# 15-SDRAM_Flash.net
KiCad netlist of a schematic drawn in Altium Designer
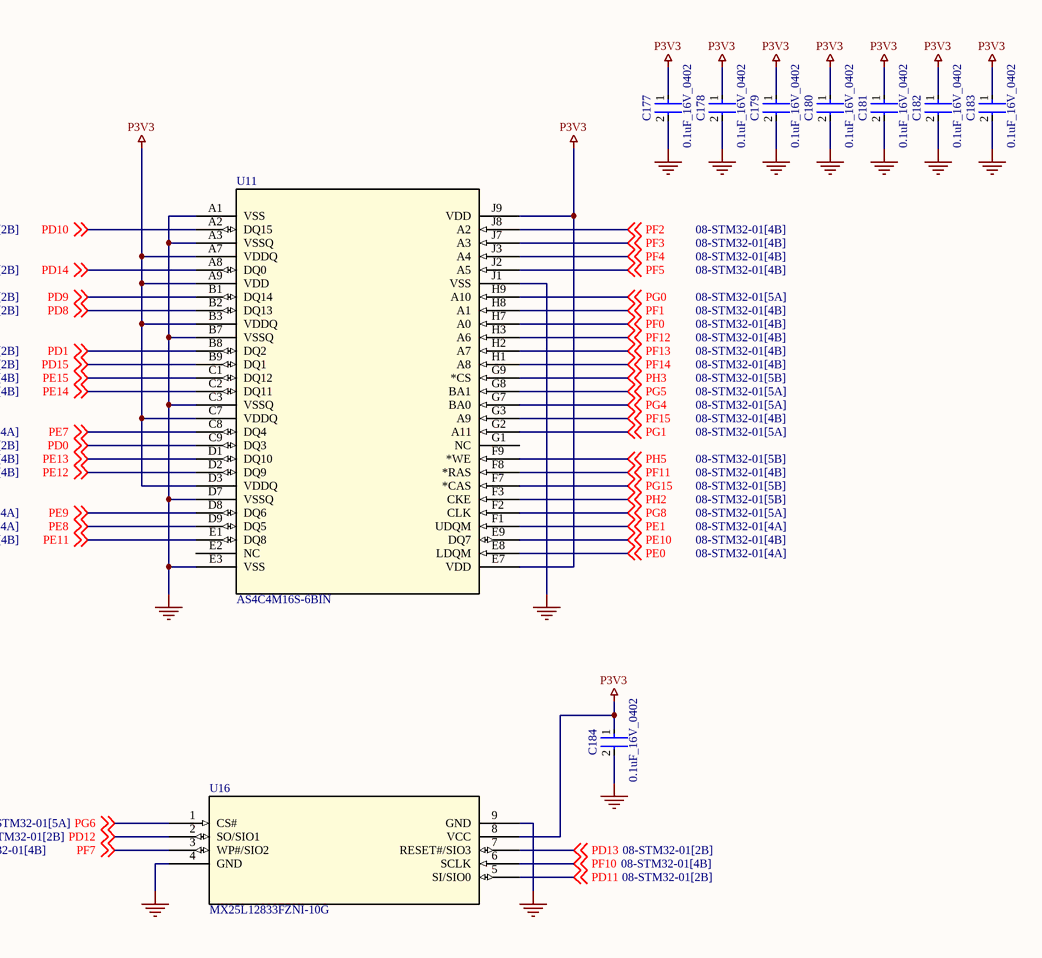
[diagram p0: 15-SDRAM_Flash.SchDoc]

(export (version "E")
  (design (tool "Eeschema 10.0.6"))
  (components
    (comp (ref "C177")
      (value "0.1uF_16V_0402")
      (footprint "FP-C0402-BB-MFG")
      (description "CAP CER 0.1UF 16V 5% X7R 0402")
      (fields
        (field (name "MANUFACTURER") "Kemet")
        (field (name "MANUFACTURER PART NUMBER") "C0402C104J4RACTU")
      )
      (libsource (lib "Altium Content Vault") (part "b4654b650e69147ec39a6b967a45e02"))
    )
    (comp (ref "C178")
      (value "0.1uF_16V_0402")
      (footprint "FP-C0402-BB-MFG")
      (description "CAP CER 0.1UF 16V 5% X7R 0402")
      (fields
        (field (name "MANUFACTURER") "Kemet")
        (field (name "MANUFACTURER PART NUMBER") "C0402C104J4RACTU")
      )
      (libsource (lib "Altium Content Vault") (part "b4654b650e69147ec39a6b967a45e02"))
    )
    (comp (ref "C179")
      (value "0.1uF_16V_0402")
      (footprint "FP-C0402-BB-MFG")
      (description "CAP CER 0.1UF 16V 5% X7R 0402")
      (fields
        (field (name "MANUFACTURER") "Kemet")
        (field (name "MANUFACTURER PART NUMBER") "C0402C104J4RACTU")
      )
      (libsource (lib "Altium Content Vault") (part "b4654b650e69147ec39a6b967a45e02"))
    )
    (comp (ref "C180")
      (value "0.1uF_16V_0402")
      (footprint "FP-C0402-BB-MFG")
      (description "CAP CER 0.1UF 16V 5% X7R 0402")
      (fields
        (field (name "MANUFACTURER") "Kemet")
        (field (name "MANUFACTURER PART NUMBER") "C0402C104J4RACTU")
      )
      (libsource (lib "Altium Content Vault") (part "b4654b650e69147ec39a6b967a45e02"))
    )
    (comp (ref "C181")
      (value "0.1uF_16V_0402")
      (footprint "FP-C0402-BB-MFG")
      (description "CAP CER 0.1UF 16V 5% X7R 0402")
      (fields
        (field (name "MANUFACTURER") "Kemet")
        (field (name "MANUFACTURER PART NUMBER") "C0402C104J4RACTU")
      )
      (libsource (lib "Altium Content Vault") (part "b4654b650e69147ec39a6b967a45e02"))
    )
    (comp (ref "C182")
      (value "0.1uF_16V_0402")
      (footprint "FP-C0402-BB-MFG")
      (description "CAP CER 0.1UF 16V 5% X7R 0402")
      (fields
        (field (name "MANUFACTURER") "Kemet")
        (field (name "MANUFACTURER PART NUMBER") "C0402C104J4RACTU")
      )
      (libsource (lib "Altium Content Vault") (part "b4654b650e69147ec39a6b967a45e02"))
    )
    (comp (ref "C183")
      (value "0.1uF_16V_0402")
      (footprint "FP-C0402-BB-MFG")
      (description "CAP CER 0.1UF 16V 5% X7R 0402")
      (fields
        (field (name "MANUFACTURER") "Kemet")
        (field (name "MANUFACTURER PART NUMBER") "C0402C104J4RACTU")
      )
      (libsource (lib "Altium Content Vault") (part "b4654b650e69147ec39a6b967a45e02"))
    )
    (comp (ref "C184")
      (value "0.1uF_16V_0402")
      (footprint "FP-C0402-BB-MFG")
      (description "CAP CER 0.1UF 16V 5% X7R 0402")
      (fields
        (field (name "MANUFACTURER") "Kemet")
        (field (name "MANUFACTURER PART NUMBER") "C0402C104J4RACTU")
      )
      (libsource (lib "Altium Content Vault") (part "b4654b650e69147ec39a6b967a45e02"))
    )
    (comp (ref "U11")
      (value "AS4C4M16S-6BIN")
      (footprint "TFBGA-54_8X8_ALL")
      (description "No Description Available")
      (fields (field (name "COPYRIGHT") "Copyright (C) 2023 Ultra Librarian. All rights reserved."))
      (libsource (lib "AS4C4M16S-6BIN") (part "AS4C4M16S-6BIN"))
    )
    (comp (ref "U16")
      (value "MX25L12833FZNI-10G")
      (footprint "WSON8_6X5X0p8_MAC")
      (description "No Description Available")
      (fields (field (name "COPYRIGHT") "Copyright (C) 2023 Ultra Librarian. All rights reserved."))
      (libsource (lib "MX25L12833FZNI-10G") (part "MX25L12833FZNI-10G"))
    )
  )
  (nets
    (net (code "1") (name "GND") (class "Default")
      (node (ref "C177") (pin "2") (pinfunction "2_2") (pintype "passive"))
      (node (ref "C178") (pin "2") (pinfunction "2_2") (pintype "passive"))
      (node (ref "C179") (pin "2") (pinfunction "2_2") (pintype "passive"))
      (node (ref "C180") (pin "2") (pinfunction "2_2") (pintype "passive"))
      (node (ref "C181") (pin "2") (pinfunction "2_2") (pintype "passive"))
      (node (ref "C182") (pin "2") (pinfunction "2_2") (pintype "passive"))
      (node (ref "C183") (pin "2") (pinfunction "2_2") (pintype "passive"))
      (node (ref "C184") (pin "2") (pinfunction "2_2") (pintype "passive"))
      (node (ref "U11") (pin "A1") (pinfunction "VSS_A1") (pintype "power_in"))
      (node (ref "U11") (pin "A3") (pinfunction "VSSQ_A3") (pintype "power_in"))
      (node (ref "U11") (pin "B7") (pinfunction "VSSQ_B7") (pintype "power_in"))
      (node (ref "U11") (pin "C3") (pinfunction "VSSQ_C3") (pintype "power_in"))
      (node (ref "U11") (pin "D7") (pinfunction "VSSQ_D7") (pintype "power_in"))
      (node (ref "U11") (pin "E3") (pinfunction "VSS_E3") (pintype "power_in"))
      (node (ref "U11") (pin "J1") (pinfunction "VSS_J1") (pintype "power_in"))
      (node (ref "U16") (pin "4") (pinfunction "GND_4") (pintype "power_in"))
      (node (ref "U16") (pin "9") (pinfunction "GND_9") (pintype "power_in"))
    )
    (net (code "2") (name "P3V3") (class "Default")
      (node (ref "C177") (pin "1") (pinfunction "1_1") (pintype "passive"))
      (node (ref "C178") (pin "1") (pinfunction "1_1") (pintype "passive"))
      (node (ref "C179") (pin "1") (pinfunction "1_1") (pintype "passive"))
      (node (ref "C180") (pin "1") (pinfunction "1_1") (pintype "passive"))
      (node (ref "C181") (pin "1") (pinfunction "1_1") (pintype "passive"))
      (node (ref "C182") (pin "1") (pinfunction "1_1") (pintype "passive"))
      (node (ref "C183") (pin "1") (pinfunction "1_1") (pintype "passive"))
      (node (ref "C184") (pin "1") (pinfunction "1_1") (pintype "passive"))
      (node (ref "U11") (pin "A7") (pinfunction "VDDQ_A7") (pintype "power_in"))
      (node (ref "U11") (pin "A9") (pinfunction "VDD_A9") (pintype "power_in"))
      (node (ref "U11") (pin "B3") (pinfunction "VDDQ_B3") (pintype "power_in"))
      (node (ref "U11") (pin "C7") (pinfunction "VDDQ_C7") (pintype "power_in"))
      (node (ref "U11") (pin "D3") (pinfunction "VDDQ_D3") (pintype "power_in"))
      (node (ref "U11") (pin "E7") (pinfunction "VDD_E7") (pintype "power_in"))
      (node (ref "U11") (pin "J9") (pinfunction "VDD_J9") (pintype "power_in"))
      (node (ref "U16") (pin "8") (pinfunction "VCC_8") (pintype "power_in"))
    )
    (net (code "3") (name "PD0") (class "Default")
      (node (ref "U11") (pin "C9") (pinfunction "DQ3_C9") (pintype "bidirectional"))
    )
    (net (code "4") (name "PD1") (class "Default")
      (node (ref "U11") (pin "B8") (pinfunction "DQ2_B8") (pintype "bidirectional"))
    )
    (net (code "5") (name "PD8") (class "Default")
      (node (ref "U11") (pin "B2") (pinfunction "DQ13_B2") (pintype "bidirectional"))
    )
    (net (code "6") (name "PD9") (class "Default")
      (node (ref "U11") (pin "B1") (pinfunction "DQ14_B1") (pintype "bidirectional"))
    )
    (net (code "7") (name "PD10") (class "Default")
      (node (ref "U11") (pin "A2") (pinfunction "DQ15_A2") (pintype "bidirectional"))
    )
    (net (code "8") (name "PD11") (class "Default")
      (node (ref "U16") (pin "5") (pinfunction "SI/SIO0_5") (pintype "bidirectional"))
    )
    (net (code "9") (name "PD12") (class "Default")
      (node (ref "U16") (pin "2") (pinfunction "SO/SIO1_2") (pintype "bidirectional"))
    )
    (net (code "10") (name "PD13") (class "Default")
      (node (ref "U16") (pin "7") (pinfunction "RESET#/SIO3_7") (pintype "bidirectional"))
    )
    (net (code "11") (name "PD14") (class "Default")
      (node (ref "U11") (pin "A8") (pinfunction "DQ0_A8") (pintype "bidirectional"))
    )
    (net (code "12") (name "PD15") (class "Default")
      (node (ref "U11") (pin "B9") (pinfunction "DQ1_B9") (pintype "bidirectional"))
    )
    (net (code "13") (name "PE0") (class "Default")
      (node (ref "U11") (pin "E8") (pinfunction "LDQM_E8") (pintype "input"))
    )
    (net (code "14") (name "PE1") (class "Default")
      (node (ref "U11") (pin "F1") (pinfunction "UDQM_F1") (pintype "input"))
    )
    (net (code "15") (name "PE7") (class "Default")
      (node (ref "U11") (pin "C8") (pinfunction "DQ4_C8") (pintype "bidirectional"))
    )
    (net (code "16") (name "PE8") (class "Default")
      (node (ref "U11") (pin "D9") (pinfunction "DQ5_D9") (pintype "bidirectional"))
    )
    (net (code "17") (name "PE9") (class "Default")
      (node (ref "U11") (pin "D8") (pinfunction "DQ6_D8") (pintype "bidirectional"))
    )
    (net (code "18") (name "PE10") (class "Default")
      (node (ref "U11") (pin "E9") (pinfunction "DQ7_E9") (pintype "bidirectional"))
    )
    (net (code "19") (name "PE11") (class "Default")
      (node (ref "U11") (pin "E1") (pinfunction "DQ8_E1") (pintype "bidirectional"))
    )
    (net (code "20") (name "PE12") (class "Default")
      (node (ref "U11") (pin "D2") (pinfunction "DQ9_D2") (pintype "bidirectional"))
    )
    (net (code "21") (name "PE13") (class "Default")
      (node (ref "U11") (pin "D1") (pinfunction "DQ10_D1") (pintype "bidirectional"))
    )
    (net (code "22") (name "PE14") (class "Default")
      (node (ref "U11") (pin "C2") (pinfunction "DQ11_C2") (pintype "bidirectional"))
    )
    (net (code "23") (name "PE15") (class "Default")
      (node (ref "U11") (pin "C1") (pinfunction "DQ12_C1") (pintype "bidirectional"))
    )
    (net (code "24") (name "PF0") (class "Default")
      (node (ref "U11") (pin "H7") (pinfunction "A0_H7") (pintype "input"))
    )
    (net (code "25") (name "PF1") (class "Default")
      (node (ref "U11") (pin "H8") (pinfunction "A1_H8") (pintype "input"))
    )
    (net (code "26") (name "PF2") (class "Default")
      (node (ref "U11") (pin "J8") (pinfunction "A2_J8") (pintype "input"))
    )
    (net (code "27") (name "PF3") (class "Default")
      (node (ref "U11") (pin "J7") (pinfunction "A3_J7") (pintype "input"))
    )
    (net (code "28") (name "PF4") (class "Default")
      (node (ref "U11") (pin "J3") (pinfunction "A4_J3") (pintype "input"))
    )
    (net (code "29") (name "PF5") (class "Default")
      (node (ref "U11") (pin "J2") (pinfunction "A5_J2") (pintype "input"))
    )
    (net (code "30") (name "PF7") (class "Default")
      (node (ref "U16") (pin "3") (pinfunction "WP#/SIO2_3") (pintype "bidirectional"))
    )
    (net (code "31") (name "PF10") (class "Default")
      (node (ref "U16") (pin "6") (pinfunction "SCLK_6") (pintype "input"))
    )
    (net (code "32") (name "PF11") (class "Default")
      (node (ref "U11") (pin "F8") (pinfunction "*RAS_F8") (pintype "input"))
    )
    (net (code "33") (name "PF12") (class "Default")
      (node (ref "U11") (pin "H3") (pinfunction "A6_H3") (pintype "input"))
    )
    (net (code "34") (name "PF13") (class "Default")
      (node (ref "U11") (pin "H2") (pinfunction "A7_H2") (pintype "input"))
    )
    (net (code "35") (name "PF14") (class "Default")
      (node (ref "U11") (pin "H1") (pinfunction "A8_H1") (pintype "input"))
    )
    (net (code "36") (name "PF15") (class "Default")
      (node (ref "U11") (pin "G3") (pinfunction "A9_G3") (pintype "input"))
    )
    (net (code "37") (name "PG0") (class "Default")
      (node (ref "U11") (pin "H9") (pinfunction "A10_H9") (pintype "input"))
    )
    (net (code "38") (name "PG1") (class "Default")
      (node (ref "U11") (pin "G2") (pinfunction "A11_G2") (pintype "input"))
    )
    (net (code "39") (name "PG4") (class "Default")
      (node (ref "U11") (pin "G7") (pinfunction "BA0_G7") (pintype "input"))
    )
    (net (code "40") (name "PG5") (class "Default")
      (node (ref "U11") (pin "G8") (pinfunction "BA1_G8") (pintype "input"))
    )
    (net (code "41") (name "PG6") (class "Default")
      (node (ref "U16") (pin "1") (pinfunction "CS#_1") (pintype "input"))
    )
    (net (code "42") (name "PG8") (class "Default")
      (node (ref "U11") (pin "F2") (pinfunction "CLK_F2") (pintype "input"))
    )
    (net (code "43") (name "PG15") (class "Default")
      (node (ref "U11") (pin "F7") (pinfunction "*CAS_F7") (pintype "input"))
    )
    (net (code "44") (name "PH2") (class "Default")
      (node (ref "U11") (pin "F3") (pinfunction "CKE_F3") (pintype "input"))
    )
    (net (code "45") (name "PH3") (class "Default")
      (node (ref "U11") (pin "G9") (pinfunction "*CS_G9") (pintype "input"))
    )
    (net (code "46") (name "PH5") (class "Default")
      (node (ref "U11") (pin "F9") (pinfunction "*WE_F9") (pintype "input"))
    )
    (net (code "47") (name "unconnected-(U11-NC-PadE2)") (class "Default")
      (node (ref "U11") (pin "E2") (pinfunction "NC_E2") (pintype "passive"))
    )
    (net (code "48") (name "unconnected-(U11-NC-PadG1)") (class "Default")
      (node (ref "U11") (pin "G1") (pinfunction "NC_G1") (pintype "passive"))
    )
  )
)
